# PX2_Header.net
KiCad netlist of a schematic drawn in Altium Designer
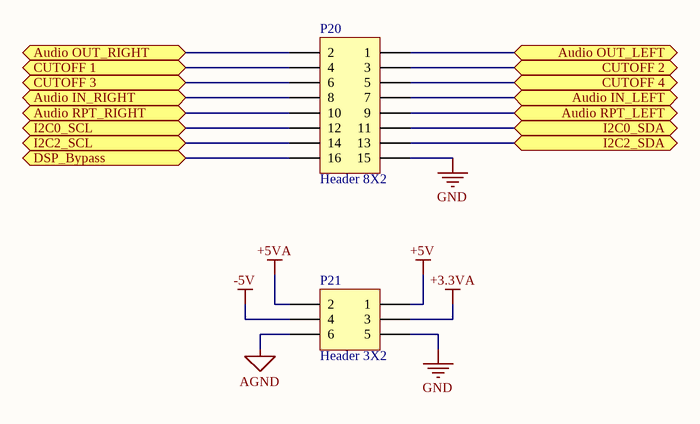
[diagram p0: PX2_Header.SchDoc]

(export (version "E")
  (design (tool "Eeschema 10.0.6"))
  (components
    (comp (ref "P20")
      (value "Header 8X2")
      (footprint "CONN_1241050-8_T")
      (description "Header, 8-Pin, Dual row")
      (libsource (lib "Miscellaneous Connectors") (part "Header 8X2"))
    )
    (comp (ref "P21")
      (value "Header 3X2")
      (footprint "CONN_1241050-3_T")
      (description "Header, 3-Pin, Dual row")
      (libsource (lib "Miscellaneous Connectors") (part "Header 3X2"))
    )
  )
  (nets
    (net (code "1") (name "+3.3VA") (class "Default")
      (node (ref "P21") (pin "3") (pinfunction "3_3") (pintype "passive"))
    )
    (net (code "2") (name "+5V") (class "Default")
      (node (ref "P21") (pin "1") (pinfunction "1_1") (pintype "passive"))
    )
    (net (code "3") (name "+5VA") (class "Default")
      (node (ref "P21") (pin "2") (pinfunction "2_2") (pintype "passive"))
    )
    (net (code "4") (name "-5V") (class "Default")
      (node (ref "P21") (pin "4") (pinfunction "4_4") (pintype "passive"))
    )
    (net (code "5") (name "/Audio IN_LEFT") (class "Default")
      (node (ref "P20") (pin "7") (pinfunction "7_7") (pintype "passive"))
    )
    (net (code "6") (name "/Audio IN_RIGHT") (class "Default")
      (node (ref "P20") (pin "8") (pinfunction "8_8") (pintype "passive"))
    )
    (net (code "7") (name "/Audio OUT_LEFT") (class "Default")
      (node (ref "P20") (pin "1") (pinfunction "1_1") (pintype "passive"))
    )
    (net (code "8") (name "/Audio OUT_RIGHT") (class "Default")
      (node (ref "P20") (pin "2") (pinfunction "2_2") (pintype "passive"))
    )
    (net (code "9") (name "/Audio RPT_LEFT") (class "Default")
      (node (ref "P20") (pin "9") (pinfunction "9_9") (pintype "passive"))
    )
    (net (code "10") (name "/Audio RPT_RIGHT") (class "Default")
      (node (ref "P20") (pin "10") (pinfunction "10_10") (pintype "passive"))
    )
    (net (code "11") (name "/CUTOFF 1") (class "Default")
      (node (ref "P20") (pin "4") (pinfunction "4_4") (pintype "passive"))
    )
    (net (code "12") (name "/CUTOFF 2") (class "Default")
      (node (ref "P20") (pin "3") (pinfunction "3_3") (pintype "passive"))
    )
    (net (code "13") (name "/CUTOFF 3") (class "Default")
      (node (ref "P20") (pin "6") (pinfunction "6_6") (pintype "passive"))
    )
    (net (code "14") (name "/CUTOFF 4") (class "Default")
      (node (ref "P20") (pin "5") (pinfunction "5_5") (pintype "passive"))
    )
    (net (code "15") (name "/DSP_Bypass") (class "Default")
      (node (ref "P20") (pin "16") (pinfunction "16_16") (pintype "passive"))
    )
    (net (code "16") (name "/I2C0_SCL") (class "Default")
      (node (ref "P20") (pin "12") (pinfunction "12_12") (pintype "passive"))
    )
    (net (code "17") (name "/I2C0_SDA") (class "Default")
      (node (ref "P20") (pin "11") (pinfunction "11_11") (pintype "passive"))
    )
    (net (code "18") (name "/I2C2_SCL") (class "Default")
      (node (ref "P20") (pin "14") (pinfunction "14_14") (pintype "passive"))
    )
    (net (code "19") (name "/I2C2_SDA") (class "Default")
      (node (ref "P20") (pin "13") (pinfunction "13_13") (pintype "passive"))
    )
    (net (code "20") (name "AGND") (class "Default")
      (node (ref "P21") (pin "6") (pinfunction "6_6") (pintype "passive"))
    )
    (net (code "21") (name "GND") (class "Default")
      (node (ref "P20") (pin "15") (pinfunction "15_15") (pintype "passive"))
      (node (ref "P21") (pin "5") (pinfunction "5_5") (pintype "passive"))
    )
  )
)
